# Main_Shield_Board.net
KiCad netlist of a schematic drawn in Altium Designer
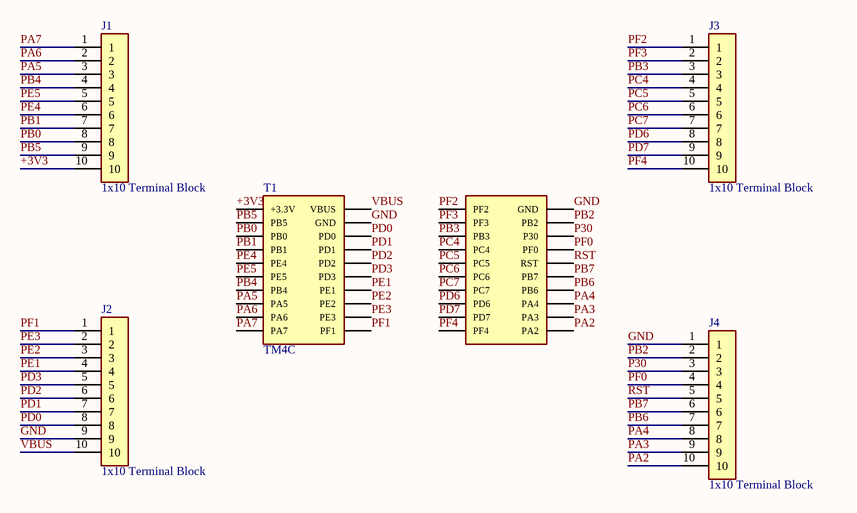
[diagram p0: Main Shield Board.SchDoc]

(export (version "E")
  (design (tool "Eeschema 10.0.6"))
  (components
    (comp (ref "J1")
      (value "1x10 Terminal Block")
      (footprint "PHOENIX_1988888")
      (description "Conn PC Terminal Block 10 POS 5mm Solder Thru-Hole 17.5A")
      (fields
        (field (name "MANUFACTURER") "Phoenix Contact")
        (field (name "MANUFACTURER PART NUMBER") "1988888")
      )
      (libsource (lib "Main Shield Board") (part "1988888"))
    )
    (comp (ref "J2")
      (value "1x10 Terminal Block")
      (footprint "PHOENIX_1988888")
      (description "Conn PC Terminal Block 10 POS 5mm Solder Thru-Hole 17.5A")
      (fields
        (field (name "MANUFACTURER") "Phoenix Contact")
        (field (name "MANUFACTURER PART NUMBER") "1988888")
      )
      (libsource (lib "Main Shield Board") (part "1988888"))
    )
    (comp (ref "J3")
      (value "1x10 Terminal Block")
      (footprint "PHOENIX_1988888")
      (description "Conn PC Terminal Block 10 POS 5mm Solder Thru-Hole 17.5A")
      (fields
        (field (name "MANUFACTURER") "Phoenix Contact")
        (field (name "MANUFACTURER PART NUMBER") "1988888")
      )
      (libsource (lib "Main Shield Board") (part "1988888"))
    )
    (comp (ref "J4")
      (value "1x10 Terminal Block")
      (footprint "PHOENIX_1988888")
      (description "Conn PC Terminal Block 10 POS 5mm Solder Thru-Hole 17.5A")
      (fields
        (field (name "MANUFACTURER") "Phoenix Contact")
        (field (name "MANUFACTURER PART NUMBER") "1988888")
      )
      (libsource (lib "Main Shield Board") (part "1988888"))
    )
    (comp (ref "T1")
      (value "TM4C")
      (footprint "SAMTEC_TSW-110-23-S-D")
      (libsource (lib "Main Shield Board") (part "TM4C"))
    )
  )
  (nets
    (net (code "1") (name "/+3V3") (class "Default")
      (node (ref "J1") (pin "10") (pinfunction "10_10") (pintype "passive"))
      (node (ref "T1") (pin "+3.3V") (pinfunction "+3.3V_+3.3V") (pintype "power_in"))
    )
    (net (code "2") (name "/GND") (class "Default")
      (node (ref "J2") (pin "9") (pinfunction "9_9") (pintype "passive"))
      (node (ref "J4") (pin "1") (pinfunction "1_1") (pintype "passive"))
      (node (ref "T1") (pin "GND") (pinfunction "GND_GND") (pintype "passive"))
    )
    (net (code "3") (name "/P30") (class "Default")
      (node (ref "J4") (pin "3") (pinfunction "3_3") (pintype "passive"))
      (node (ref "T1") (pin "P30") (pinfunction "P30_P30") (pintype "passive"))
    )
    (net (code "4") (name "/PA2") (class "Default")
      (node (ref "J4") (pin "10") (pinfunction "10_10") (pintype "passive"))
      (node (ref "T1") (pin "PA2") (pinfunction "PA2_PA2") (pintype "passive"))
    )
    (net (code "5") (name "/PA3") (class "Default")
      (node (ref "J4") (pin "9") (pinfunction "9_9") (pintype "passive"))
      (node (ref "T1") (pin "PA3") (pinfunction "PA3_PA3") (pintype "passive"))
    )
    (net (code "6") (name "/PA4") (class "Default")
      (node (ref "J4") (pin "8") (pinfunction "8_8") (pintype "passive"))
      (node (ref "T1") (pin "PA4") (pinfunction "PA4_PA4") (pintype "passive"))
    )
    (net (code "7") (name "/PA5") (class "Default")
      (node (ref "J1") (pin "3") (pinfunction "3_3") (pintype "passive"))
      (node (ref "T1") (pin "PA5") (pinfunction "PA5_PA5") (pintype "passive"))
    )
    (net (code "8") (name "/PA6") (class "Default")
      (node (ref "J1") (pin "2") (pinfunction "2_2") (pintype "passive"))
      (node (ref "T1") (pin "PA6") (pinfunction "PA6_PA6") (pintype "passive"))
    )
    (net (code "9") (name "/PA7") (class "Default")
      (node (ref "J1") (pin "1") (pinfunction "1_1") (pintype "passive"))
      (node (ref "T1") (pin "PA7") (pinfunction "PA7_PA7") (pintype "passive"))
    )
    (net (code "10") (name "/PB0") (class "Default")
      (node (ref "J1") (pin "8") (pinfunction "8_8") (pintype "passive"))
      (node (ref "T1") (pin "PB0") (pinfunction "PB0_PB0") (pintype "passive"))
    )
    (net (code "11") (name "/PB1") (class "Default")
      (node (ref "J1") (pin "7") (pinfunction "7_7") (pintype "passive"))
      (node (ref "T1") (pin "PB1") (pinfunction "PB1_PB1") (pintype "passive"))
    )
    (net (code "12") (name "/PB2") (class "Default")
      (node (ref "J4") (pin "2") (pinfunction "2_2") (pintype "passive"))
      (node (ref "T1") (pin "PB2") (pinfunction "PB2_PB2") (pintype "passive"))
    )
    (net (code "13") (name "/PB3") (class "Default")
      (node (ref "J3") (pin "3") (pinfunction "3_3") (pintype "passive"))
      (node (ref "T1") (pin "PB3") (pinfunction "PB3_PB3") (pintype "passive"))
    )
    (net (code "14") (name "/PB4") (class "Default")
      (node (ref "J1") (pin "4") (pinfunction "4_4") (pintype "passive"))
      (node (ref "T1") (pin "PB4") (pinfunction "PB4_PB4") (pintype "passive"))
    )
    (net (code "15") (name "/PB5") (class "Default")
      (node (ref "J1") (pin "9") (pinfunction "9_9") (pintype "passive"))
      (node (ref "T1") (pin "PB5") (pinfunction "PB5_PB5") (pintype "passive"))
    )
    (net (code "16") (name "/PB6") (class "Default")
      (node (ref "J4") (pin "7") (pinfunction "7_7") (pintype "passive"))
      (node (ref "T1") (pin "PB6") (pinfunction "PB6_PB6") (pintype "passive"))
    )
    (net (code "17") (name "/PB7") (class "Default")
      (node (ref "J4") (pin "6") (pinfunction "6_6") (pintype "passive"))
      (node (ref "T1") (pin "PB7") (pinfunction "PB7_PB7") (pintype "passive"))
    )
    (net (code "18") (name "/PC4") (class "Default")
      (node (ref "J3") (pin "4") (pinfunction "4_4") (pintype "passive"))
      (node (ref "T1") (pin "PC4") (pinfunction "PC4_PC4") (pintype "passive"))
    )
    (net (code "19") (name "/PC5") (class "Default")
      (node (ref "J3") (pin "5") (pinfunction "5_5") (pintype "passive"))
      (node (ref "T1") (pin "PC5") (pinfunction "PC5_PC5") (pintype "passive"))
    )
    (net (code "20") (name "/PC6") (class "Default")
      (node (ref "J3") (pin "6") (pinfunction "6_6") (pintype "passive"))
      (node (ref "T1") (pin "PC6") (pinfunction "PC6_PC6") (pintype "passive"))
    )
    (net (code "21") (name "/PC7") (class "Default")
      (node (ref "J3") (pin "7") (pinfunction "7_7") (pintype "passive"))
      (node (ref "T1") (pin "PC7") (pinfunction "PC7_PC7") (pintype "passive"))
    )
    (net (code "22") (name "/PD0") (class "Default")
      (node (ref "J2") (pin "8") (pinfunction "8_8") (pintype "passive"))
      (node (ref "T1") (pin "PD0") (pinfunction "PD0_PD0") (pintype "passive"))
    )
    (net (code "23") (name "/PD1") (class "Default")
      (node (ref "J2") (pin "7") (pinfunction "7_7") (pintype "passive"))
      (node (ref "T1") (pin "PD1") (pinfunction "PD1_PD1") (pintype "passive"))
    )
    (net (code "24") (name "/PD2") (class "Default")
      (node (ref "J2") (pin "6") (pinfunction "6_6") (pintype "passive"))
      (node (ref "T1") (pin "PD2") (pinfunction "PD2_PD2") (pintype "passive"))
    )
    (net (code "25") (name "/PD3") (class "Default")
      (node (ref "J2") (pin "5") (pinfunction "5_5") (pintype "passive"))
      (node (ref "T1") (pin "PD3") (pinfunction "PD3_PD3") (pintype "passive"))
    )
    (net (code "26") (name "/PD6") (class "Default")
      (node (ref "J3") (pin "8") (pinfunction "8_8") (pintype "passive"))
      (node (ref "T1") (pin "PD6") (pinfunction "PD6_PD6") (pintype "passive"))
    )
    (net (code "27") (name "/PD7") (class "Default")
      (node (ref "J3") (pin "9") (pinfunction "9_9") (pintype "passive"))
      (node (ref "T1") (pin "PD7") (pinfunction "PD7_PD7") (pintype "passive"))
    )
    (net (code "28") (name "/PE1") (class "Default")
      (node (ref "J2") (pin "4") (pinfunction "4_4") (pintype "passive"))
      (node (ref "T1") (pin "PE1") (pinfunction "PE1_PE1") (pintype "passive"))
    )
    (net (code "29") (name "/PE2") (class "Default")
      (node (ref "J2") (pin "3") (pinfunction "3_3") (pintype "passive"))
      (node (ref "T1") (pin "PE2") (pinfunction "PE2_PE2") (pintype "passive"))
    )
    (net (code "30") (name "/PE3") (class "Default")
      (node (ref "J2") (pin "2") (pinfunction "2_2") (pintype "passive"))
      (node (ref "T1") (pin "PE3") (pinfunction "PE3_PE3") (pintype "passive"))
    )
    (net (code "31") (name "/PE4") (class "Default")
      (node (ref "J1") (pin "6") (pinfunction "6_6") (pintype "passive"))
      (node (ref "T1") (pin "PE4") (pinfunction "PE4_PE4") (pintype "passive"))
    )
    (net (code "32") (name "/PE5") (class "Default")
      (node (ref "J1") (pin "5") (pinfunction "5_5") (pintype "passive"))
      (node (ref "T1") (pin "PE5") (pinfunction "PE5_PE5") (pintype "passive"))
    )
    (net (code "33") (name "/PF0") (class "Default")
      (node (ref "J4") (pin "4") (pinfunction "4_4") (pintype "passive"))
      (node (ref "T1") (pin "PF0") (pinfunction "PF0_PF0") (pintype "passive"))
    )
    (net (code "34") (name "/PF1") (class "Default")
      (node (ref "J2") (pin "1") (pinfunction "1_1") (pintype "passive"))
      (node (ref "T1") (pin "PF1") (pinfunction "PF1_PF1") (pintype "passive"))
    )
    (net (code "35") (name "/PF2") (class "Default")
      (node (ref "J3") (pin "1") (pinfunction "1_1") (pintype "passive"))
      (node (ref "T1") (pin "PF2") (pinfunction "PF2_PF2") (pintype "passive"))
    )
    (net (code "36") (name "/PF3") (class "Default")
      (node (ref "J3") (pin "2") (pinfunction "2_2") (pintype "passive"))
      (node (ref "T1") (pin "PF3") (pinfunction "PF3_PF3") (pintype "passive"))
    )
    (net (code "37") (name "/PF4") (class "Default")
      (node (ref "J3") (pin "10") (pinfunction "10_10") (pintype "passive"))
      (node (ref "T1") (pin "PF4") (pinfunction "PF4_PF4") (pintype "passive"))
    )
    (net (code "38") (name "/RST") (class "Default")
      (node (ref "J4") (pin "5") (pinfunction "5_5") (pintype "passive"))
      (node (ref "T1") (pin "RST") (pinfunction "RST_RST") (pintype "passive"))
    )
    (net (code "39") (name "/VBUS") (class "Default")
      (node (ref "J2") (pin "10") (pinfunction "10_10") (pintype "passive"))
      (node (ref "T1") (pin "VBUS") (pinfunction "VBUS_VBUS") (pintype "power_in"))
    )
  )
)
